# PickupDaughterBoard.net
KiCad netlist of a schematic drawn in EAGLE
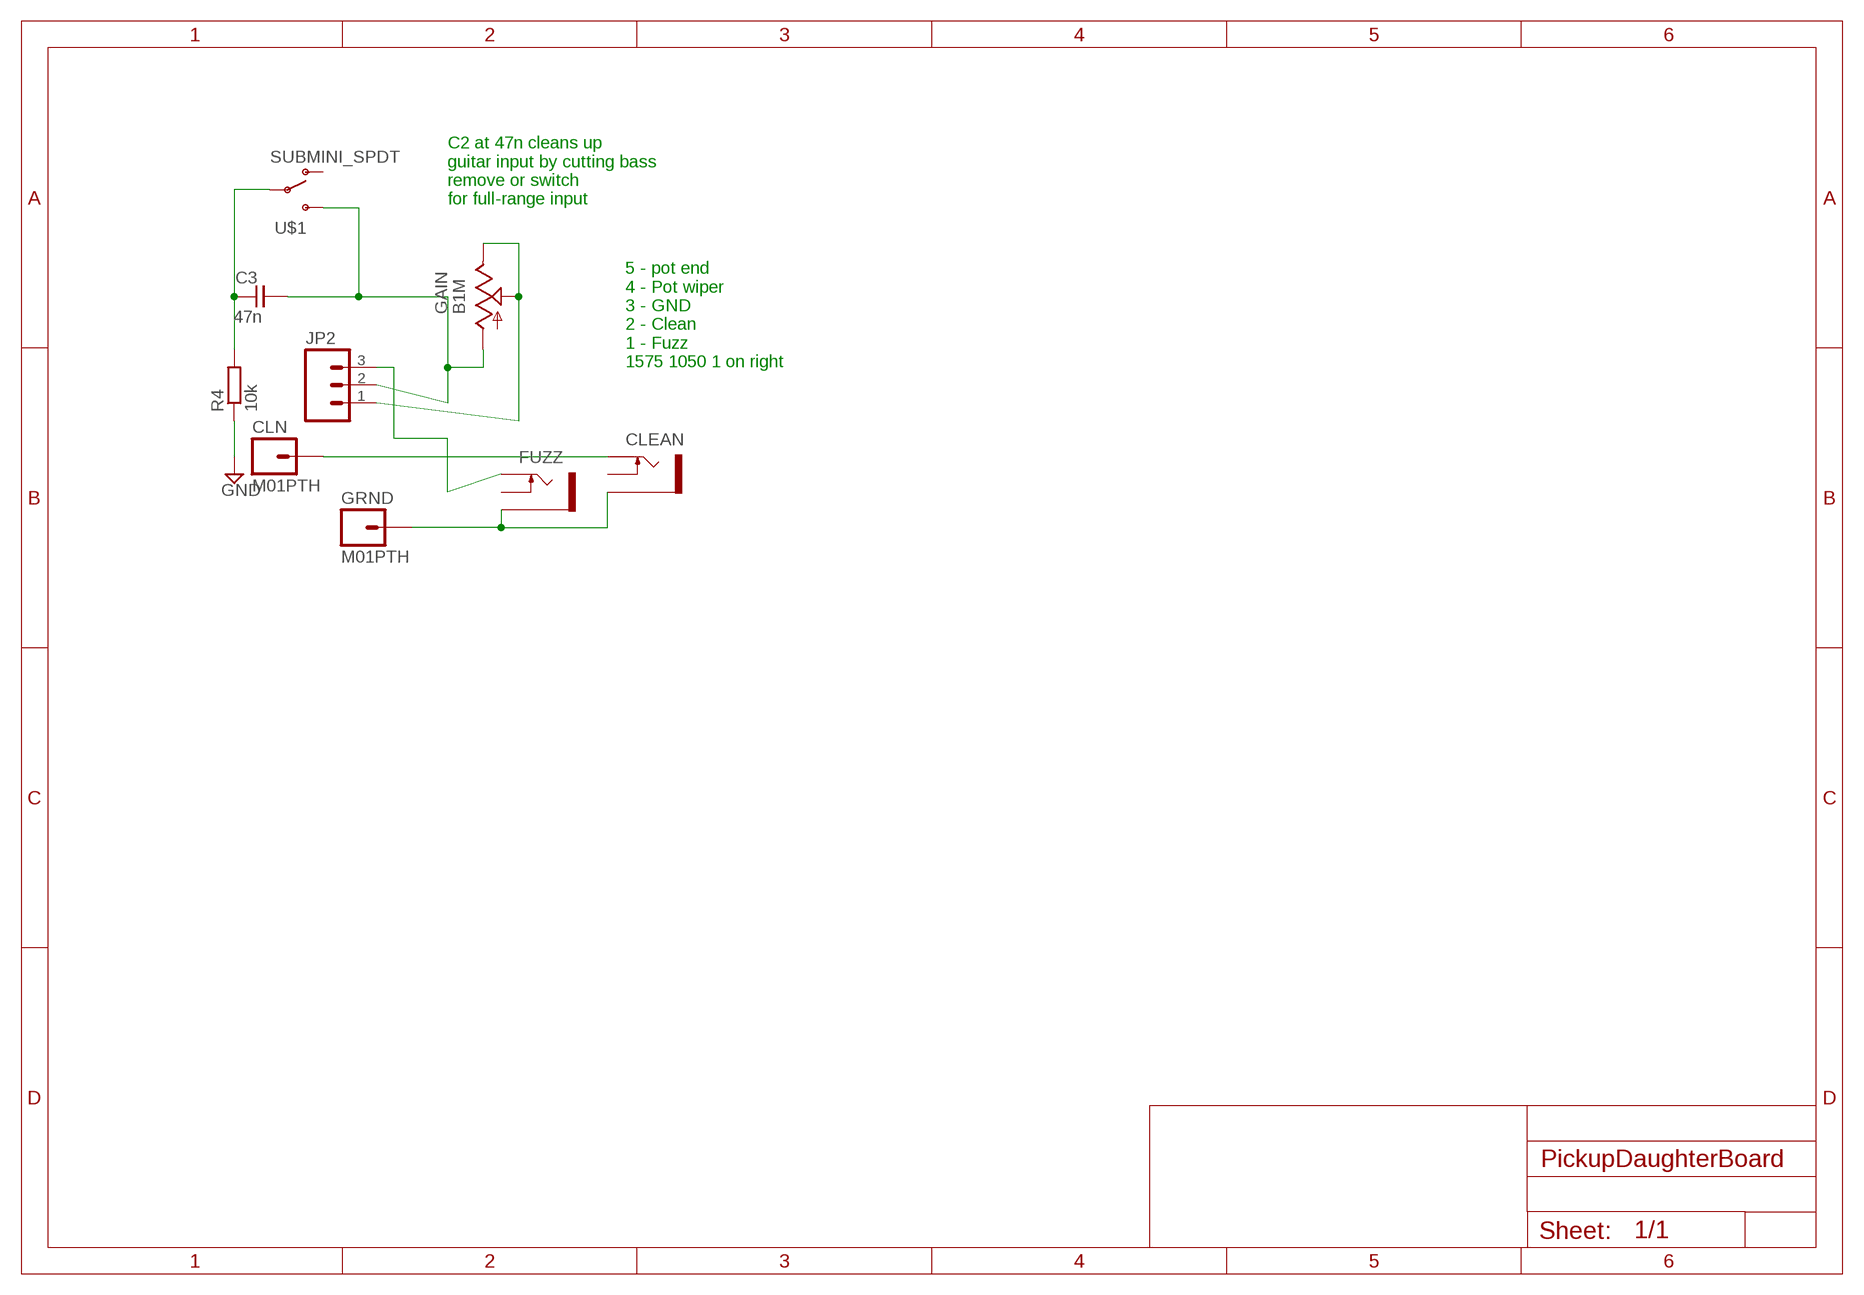
[diagram p0: schematic, sheet 1]

(export (version "E")
  (design (tool "Eeschema 10.0.6"))
  (components
    (comp (ref "C3")
      (value "47n")
      (footprint "eagle-import:C050-024X044")
      (libsource (lib "eagle-import") (part "C-EU050-024X044"))
    )
    (comp (ref "CLEAN")
      (value "THONKICONNNEW")
      (footprint "eagle-import:WQP-PJ301M-12_JACK")
      (libsource (lib "eagle-import") (part "THONKICONNNEW"))
    )
    (comp (ref "CLN")
      (value "M01PTH")
      (footprint "eagle-import:1X01")
      (libsource (lib "eagle-import") (part "M01PTH"))
    )
    (comp (ref "FUZZ")
      (value "THONKICONNNEW")
      (footprint "eagle-import:WQP-PJ301M-12_JACK")
      (libsource (lib "eagle-import") (part "THONKICONNNEW"))
    )
    (comp (ref "GAIN")
      (value "B1M")
      (footprint "eagle-import:EVUF")
      (libsource (lib "eagle-import") (part "ALPHA-9MMAF2"))
    )
    (comp (ref "GRND")
      (value "M01PTH")
      (footprint "eagle-import:1X01")
      (libsource (lib "eagle-import") (part "M01PTH"))
    )
    (comp (ref "JP2")
      (value "M03PTH")
      (footprint "eagle-import:1X03")
      (libsource (lib "eagle-import") (part "M03PTH"))
    )
    (comp (ref "R4")
      (value "10k")
      (footprint "eagle-import:VERTICAL_RESISTOR")
      (libsource (lib "eagle-import") (part "RESISTORVERTICAL"))
    )
    (comp (ref "U$1")
      (value "SUBMINI_SPDT")
      (footprint "eagle-import:SUBMINI_TOGGLE")
      (libsource (lib "eagle-import") (part "SUBMINI_SPDT"))
    )
  )
  (nets
    (net (code "1") (name "GND") (class "Default")
      (node (ref "CLEAN") (pin "P$3_SLEEVE") (pinfunction "SLEEVE_P$3_SLEEVE") (pintype "passive"))
      (node (ref "FUZZ") (pin "P$3_SLEEVE") (pinfunction "SLEEVE_P$3_SLEEVE") (pintype "passive"))
      (node (ref "GRND") (pin "1") (pinfunction "1_1") (pintype "passive"))
      (node (ref "R4") (pin "1") (pinfunction "1_1") (pintype "passive"))
    )
    (net (code "2") (name "Net-(CLEAN-TIP)") (class "Default")
      (node (ref "CLEAN") (pin "P$1_TIP") (pinfunction "TIP_P$1_TIP") (pintype "passive"))
      (node (ref "CLN") (pin "1") (pinfunction "1_1") (pintype "passive"))
    )
    (net (code "3") (name "Net-(FUZZ-TIP)") (class "Default")
      (node (ref "FUZZ") (pin "P$1_TIP") (pinfunction "TIP_P$1_TIP") (pintype "passive"))
      (node (ref "JP2") (pin "3") (pinfunction "3_3") (pintype "passive"))
    )
    (net (code "4") (name "Net-(GAIN-A)") (class "Default")
      (node (ref "C3") (pin "1") (pinfunction "1_1") (pintype "passive"))
      (node (ref "GAIN") (pin "1") (pinfunction "A_1") (pintype "passive"))
      (node (ref "JP2") (pin "2") (pinfunction "2_2") (pintype "passive"))
      (node (ref "U$1") (pin "3") (pinfunction "S_3") (pintype "passive"))
    )
    (net (code "5") (name "Net-(GAIN-E)") (class "Default")
      (node (ref "GAIN") (pin "2") (pinfunction "S_2") (pintype "passive"))
      (node (ref "GAIN") (pin "3") (pinfunction "E_3") (pintype "passive"))
      (node (ref "JP2") (pin "1") (pinfunction "1_1") (pintype "passive"))
    )
    (net (code "6") (name "Net-(U$1-COMMON)") (class "Default")
      (node (ref "C3") (pin "2") (pinfunction "2_2") (pintype "passive"))
      (node (ref "R4") (pin "2") (pinfunction "2_2") (pintype "passive"))
      (node (ref "U$1") (pin "COM") (pinfunction "COMMON_COM") (pintype "passive"))
    )
    (net (code "7") (name "unconnected-(CLEAN-SWITCH-PadP$2_SWITCH)") (class "Default")
      (node (ref "CLEAN") (pin "P$2_SWITCH") (pinfunction "SWITCH_P$2_SWITCH") (pintype "passive"))
    )
    (net (code "8") (name "unconnected-(FUZZ-SWITCH-PadP$2_SWITCH)") (class "Default")
      (node (ref "FUZZ") (pin "P$2_SWITCH") (pinfunction "SWITCH_P$2_SWITCH") (pintype "passive"))
    )
    (net (code "9") (name "unconnected-(U$1-O-Pad1)") (class "Default")
      (node (ref "U$1") (pin "1") (pinfunction "O_1") (pintype "passive"))
    )
  )
)
